# ESP.net
KiCad netlist of a schematic drawn in Altium Designer
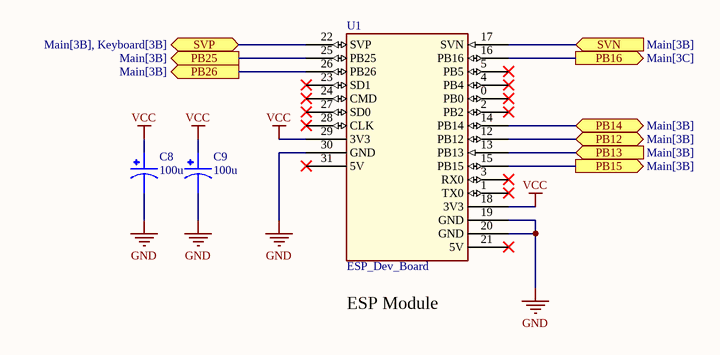
[diagram p0: ESP.SchDoc]

(export (version "E")
  (design (tool "Eeschema 10.0.6"))
  (components
    (comp (ref "C8")
      (value "100u")
      (footprint "CAPPRD500W60D1330H2700")
      (description "4700 ÂµF 10 V Aluminum Electrolytic Capacitors Radial, Can 98.8mOhm @ 120Hz 2000 Hrs @ 85Â°C")
      (fields (field (name "MF") "Illinois Capacitor") (field (name "MP") "478CKS010M"))
      (libsource (lib "478CKS010M") (part "478CKS010M"))
    )
    (comp (ref "C9")
      (value "100u")
      (footprint "CAPPRD500W60D1330H2700")
      (description "4700 ÂµF 10 V Aluminum Electrolytic Capacitors Radial, Can 98.8mOhm @ 120Hz 2000 Hrs @ 85Â°C")
      (fields (field (name "MF") "Illinois Capacitor") (field (name "MP") "478CKS010M"))
      (libsource (lib "478CKS010M") (part "478CKS010M"))
    )
    (comp (ref "U1")
      (value "ESP_Dev_Board")
      (footprint "PCB_Library_TM:ESP_Dev_Board")
      (description "ESP Dev Board with lcd")
      (libsource (lib "Schematic_Library_TM") (part "ESP_Dev_Board"))
    )
  )
  (nets
    (net (code "1") (name "/PB12") (class "Default")
      (node (ref "U1") (pin "12") (pinfunction "PB12_12") (pintype "bidirectional"))
    )
    (net (code "2") (name "/PB13") (class "Default")
      (node (ref "U1") (pin "13") (pinfunction "PB13_13") (pintype "input"))
    )
    (net (code "3") (name "/PB14") (class "Default")
      (node (ref "U1") (pin "14") (pinfunction "PB14_14") (pintype "bidirectional"))
    )
    (net (code "4") (name "/PB15") (class "Default")
      (node (ref "U1") (pin "15") (pinfunction "PB15_15") (pintype "bidirectional"))
    )
    (net (code "5") (name "/PB16") (class "Default")
      (node (ref "U1") (pin "16") (pinfunction "PB16_16") (pintype "bidirectional"))
    )
    (net (code "6") (name "/PB25") (class "Default")
      (node (ref "U1") (pin "25") (pinfunction "PB25_25") (pintype "bidirectional"))
    )
    (net (code "7") (name "/PB26") (class "Default")
      (node (ref "U1") (pin "26") (pinfunction "PB26_26") (pintype "bidirectional"))
    )
    (net (code "8") (name "/SVN") (class "Default")
      (node (ref "U1") (pin "17") (pinfunction "SVN_17") (pintype "input"))
    )
    (net (code "9") (name "/SVP") (class "Default")
      (node (ref "U1") (pin "22") (pinfunction "SVP_22") (pintype "bidirectional"))
    )
    (net (code "10") (name "GND") (class "Default")
      (node (ref "C8") (pin "2") (pinfunction "2_2") (pintype "passive"))
      (node (ref "C9") (pin "2") (pinfunction "2_2") (pintype "passive"))
      (node (ref "U1") (pin "19") (pinfunction "GND_19") (pintype "power_in"))
      (node (ref "U1") (pin "20") (pinfunction "GND_20") (pintype "power_in"))
      (node (ref "U1") (pin "30") (pinfunction "GND_30") (pintype "power_in"))
    )
    (net (code "11") (name "VCC") (class "Default")
      (node (ref "C8") (pin "1") (pinfunction "1_1") (pintype "passive"))
      (node (ref "C9") (pin "1") (pinfunction "1_1") (pintype "passive"))
      (node (ref "U1") (pin "18") (pinfunction "3V3_18") (pintype "power_in"))
      (node (ref "U1") (pin "29") (pinfunction "3V3_29") (pintype "power_in"))
    )
    (net (code "12") (name "unconnected-(U1-5V-Pad21)") (class "Default")
      (node (ref "U1") (pin "21") (pinfunction "5V_21") (pintype "power_in+no_connect"))
    )
    (net (code "13") (name "unconnected-(U1-5V-Pad31)") (class "Default")
      (node (ref "U1") (pin "31") (pinfunction "5V_31") (pintype "power_in+no_connect"))
    )
    (net (code "14") (name "unconnected-(U1-CLK-Pad28)") (class "Default")
      (node (ref "U1") (pin "28") (pinfunction "CLK_28") (pintype "bidirectional+no_connect"))
    )
    (net (code "15") (name "unconnected-(U1-CMD-Pad24)") (class "Default")
      (node (ref "U1") (pin "24") (pinfunction "CMD_24") (pintype "bidirectional+no_connect"))
    )
    (net (code "16") (name "unconnected-(U1-PB0-Pad0)") (class "Default")
      (node (ref "U1") (pin "0") (pinfunction "PB0_0") (pintype "bidirectional+no_connect"))
    )
    (net (code "17") (name "unconnected-(U1-PB2-Pad2)") (class "Default")
      (node (ref "U1") (pin "2") (pinfunction "PB2_2") (pintype "bidirectional+no_connect"))
    )
    (net (code "18") (name "unconnected-(U1-PB4-Pad4)") (class "Default")
      (node (ref "U1") (pin "4") (pinfunction "PB4_4") (pintype "bidirectional+no_connect"))
    )
    (net (code "19") (name "unconnected-(U1-PB5-Pad5)") (class "Default")
      (node (ref "U1") (pin "5") (pinfunction "PB5_5") (pintype "bidirectional+no_connect"))
    )
    (net (code "20") (name "unconnected-(U1-RX0-Pad3)") (class "Default")
      (node (ref "U1") (pin "3") (pinfunction "RX0_3") (pintype "bidirectional+no_connect"))
    )
    (net (code "21") (name "unconnected-(U1-SD0-Pad27)") (class "Default")
      (node (ref "U1") (pin "27") (pinfunction "SD0_27") (pintype "bidirectional+no_connect"))
    )
    (net (code "22") (name "unconnected-(U1-SD1-Pad23)") (class "Default")
      (node (ref "U1") (pin "23") (pinfunction "SD1_23") (pintype "bidirectional+no_connect"))
    )
    (net (code "23") (name "unconnected-(U1-TX0-Pad1)") (class "Default")
      (node (ref "U1") (pin "1") (pinfunction "TX0_1") (pintype "bidirectional+no_connect"))
    )
  )
)
